# Analog_Light_Project_Improved_PCB.net
KiCad netlist of a schematic drawn in EAGLE
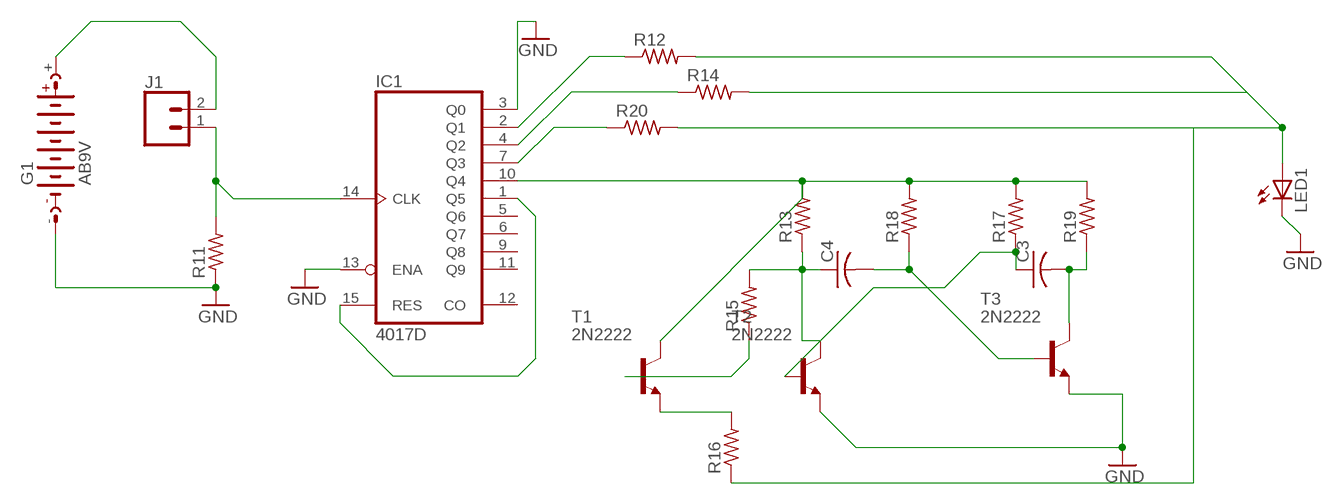
[diagram p0: schematic, sheet 1]

(export (version "E")
  (design (tool "Eeschema 10.0.6"))
  (components
    (comp (ref "C3")
      (value "C-USC0805")
      (footprint "eagle-import:C0805")
      (libsource (lib "eagle-import") (part "C-USC0805"))
    )
    (comp (ref "C4")
      (value "C-USC0805")
      (footprint "eagle-import:C0805")
      (libsource (lib "eagle-import") (part "C-USC0805"))
    )
    (comp (ref "G1")
      (value "AB9V")
      (footprint "eagle-import:AB9V")
      (libsource (lib "eagle-import") (part "AB9V"))
    )
    (comp (ref "IC1")
      (value "4017D")
      (footprint "eagle-import:SO16")
      (libsource (lib "eagle-import") (part "4017D"))
    )
    (comp (ref "J1")
      (value "CONN_02")
      (footprint "eagle-import:1X02")
      (libsource (lib "eagle-import") (part "CONN_02"))
    )
    (comp (ref "LED1")
      (value "LED5MM")
      (footprint "eagle-import:LED5MM")
      (libsource (lib "eagle-import") (part "LED5MM"))
    )
    (comp (ref "R11")
      (value "R-US_M0805")
      (footprint "eagle-import:M0805")
      (libsource (lib "eagle-import") (part "R-US_M0805"))
    )
    (comp (ref "R12")
      (value "R-US_M0805")
      (footprint "eagle-import:M0805")
      (libsource (lib "eagle-import") (part "R-US_M0805"))
    )
    (comp (ref "R13")
      (value "R-US_M0805")
      (footprint "eagle-import:M0805")
      (libsource (lib "eagle-import") (part "R-US_M0805"))
    )
    (comp (ref "R14")
      (value "R-US_M0805")
      (footprint "eagle-import:M0805")
      (libsource (lib "eagle-import") (part "R-US_M0805"))
    )
    (comp (ref "R15")
      (value "R-US_M0805")
      (footprint "eagle-import:M0805")
      (libsource (lib "eagle-import") (part "R-US_M0805"))
    )
    (comp (ref "R16")
      (value "R-US_M0805")
      (footprint "eagle-import:M0805")
      (libsource (lib "eagle-import") (part "R-US_M0805"))
    )
    (comp (ref "R17")
      (value "R-US_M0805")
      (footprint "eagle-import:M0805")
      (libsource (lib "eagle-import") (part "R-US_M0805"))
    )
    (comp (ref "R18")
      (value "R-US_M0805")
      (footprint "eagle-import:M0805")
      (libsource (lib "eagle-import") (part "R-US_M0805"))
    )
    (comp (ref "R19")
      (value "R-US_M0805")
      (footprint "eagle-import:M0805")
      (libsource (lib "eagle-import") (part "R-US_M0805"))
    )
    (comp (ref "R20")
      (value "R-US_M0805")
      (footprint "eagle-import:M0805")
      (libsource (lib "eagle-import") (part "R-US_M0805"))
    )
    (comp (ref "T1")
      (value "2N2222")
      (footprint "eagle-import:TO92-EBC-OVAL")
      (libsource (lib "eagle-import") (part "2N2222"))
    )
    (comp (ref "T2")
      (value "2N2222")
      (footprint "eagle-import:TO92-EBC-OVAL")
      (libsource (lib "eagle-import") (part "2N2222"))
    )
    (comp (ref "T3")
      (value "2N2222")
      (footprint "eagle-import:TO92-EBC-OVAL")
      (libsource (lib "eagle-import") (part "2N2222"))
    )
  )
  (nets
    (net (code "1") (name "GND") (class "Default")
      (node (ref "G1") (pin "-") (pinfunction "-_-") (pintype "passive"))
      (node (ref "IC1") (pin "13") (pinfunction "ENA_13") (pintype "input"))
      (node (ref "IC1") (pin "3") (pinfunction "Q0_3") (pintype "output"))
      (node (ref "LED1") (pin "K") (pinfunction "C_K") (pintype "passive"))
      (node (ref "R11") (pin "1") (pinfunction "1_1") (pintype "passive"))
      (node (ref "T2") (pin "E") (pinfunction "E_E") (pintype "passive"))
      (node (ref "T3") (pin "E") (pinfunction "E_E") (pintype "passive"))
    )
    (net (code "2") (name "Net-(C3-Pad1)") (class "Default")
      (node (ref "C3") (pin "1") (pinfunction "1_1") (pintype "passive"))
      (node (ref "R17") (pin "1") (pinfunction "1_1") (pintype "passive"))
      (node (ref "T2") (pin "B") (pinfunction "B_B") (pintype "passive"))
    )
    (net (code "3") (name "Net-(C3-Pad2)") (class "Default")
      (node (ref "C3") (pin "2") (pinfunction "2_2") (pintype "passive"))
      (node (ref "R19") (pin "1") (pinfunction "1_1") (pintype "passive"))
      (node (ref "T3") (pin "C") (pinfunction "C_C") (pintype "passive"))
    )
    (net (code "4") (name "Net-(C4-Pad1)") (class "Default")
      (node (ref "C4") (pin "1") (pinfunction "1_1") (pintype "passive"))
      (node (ref "R13") (pin "1") (pinfunction "1_1") (pintype "passive"))
      (node (ref "R15") (pin "2") (pinfunction "2_2") (pintype "passive"))
      (node (ref "T2") (pin "C") (pinfunction "C_C") (pintype "passive"))
    )
    (net (code "5") (name "Net-(C4-Pad2)") (class "Default")
      (node (ref "C4") (pin "2") (pinfunction "2_2") (pintype "passive"))
      (node (ref "R18") (pin "1") (pinfunction "1_1") (pintype "passive"))
      (node (ref "T3") (pin "B") (pinfunction "B_B") (pintype "passive"))
    )
    (net (code "6") (name "Net-(G1-Pad+)") (class "Default")
      (node (ref "G1") (pin "+") (pinfunction "+_+") (pintype "passive"))
      (node (ref "J1") (pin "2") (pinfunction "2_2") (pintype "passive"))
    )
    (net (code "7") (name "Net-(IC1A-CLK)") (class "Default")
      (node (ref "IC1") (pin "14") (pinfunction "CLK_14") (pintype "input"))
      (node (ref "J1") (pin "1") (pinfunction "1_1") (pintype "passive"))
      (node (ref "R11") (pin "2") (pinfunction "2_2") (pintype "passive"))
    )
    (net (code "8") (name "Net-(IC1A-Q1)") (class "Default")
      (node (ref "IC1") (pin "2") (pinfunction "Q1_2") (pintype "output"))
      (node (ref "R12") (pin "1") (pinfunction "1_1") (pintype "passive"))
    )
    (net (code "9") (name "Net-(IC1A-Q2)") (class "Default")
      (node (ref "IC1") (pin "4") (pinfunction "Q2_4") (pintype "output"))
      (node (ref "R14") (pin "1") (pinfunction "1_1") (pintype "passive"))
    )
    (net (code "10") (name "Net-(IC1A-Q3)") (class "Default")
      (node (ref "IC1") (pin "7") (pinfunction "Q3_7") (pintype "output"))
      (node (ref "R20") (pin "1") (pinfunction "1_1") (pintype "passive"))
    )
    (net (code "11") (name "Net-(IC1A-Q4)") (class "Default")
      (node (ref "IC1") (pin "10") (pinfunction "Q4_10") (pintype "output"))
      (node (ref "R13") (pin "2") (pinfunction "2_2") (pintype "passive"))
      (node (ref "R17") (pin "2") (pinfunction "2_2") (pintype "passive"))
      (node (ref "R18") (pin "2") (pinfunction "2_2") (pintype "passive"))
      (node (ref "R19") (pin "2") (pinfunction "2_2") (pintype "passive"))
      (node (ref "T1") (pin "C") (pinfunction "C_C") (pintype "passive"))
    )
    (net (code "12") (name "Net-(IC1A-Q5)") (class "Default")
      (node (ref "IC1") (pin "1") (pinfunction "Q5_1") (pintype "output"))
      (node (ref "IC1") (pin "15") (pinfunction "RES_15") (pintype "input"))
    )
    (net (code "13") (name "Net-(LED1-PadA)") (class "Default")
      (node (ref "LED1") (pin "A") (pinfunction "A_A") (pintype "passive"))
      (node (ref "R12") (pin "2") (pinfunction "2_2") (pintype "passive"))
      (node (ref "R14") (pin "2") (pinfunction "2_2") (pintype "passive"))
      (node (ref "R16") (pin "1") (pinfunction "1_1") (pintype "passive"))
      (node (ref "R20") (pin "2") (pinfunction "2_2") (pintype "passive"))
    )
    (net (code "14") (name "Net-(R15-Pad1)") (class "Default")
      (node (ref "R15") (pin "1") (pinfunction "1_1") (pintype "passive"))
      (node (ref "T1") (pin "B") (pinfunction "B_B") (pintype "passive"))
    )
    (net (code "15") (name "Net-(R16-Pad2)") (class "Default")
      (node (ref "R16") (pin "2") (pinfunction "2_2") (pintype "passive"))
      (node (ref "T1") (pin "E") (pinfunction "E_E") (pintype "passive"))
    )
    (net (code "16") (name "unconnected-(IC1A-CO-Pad12)") (class "Default")
      (node (ref "IC1") (pin "12") (pinfunction "CO_12") (pintype "output"))
    )
    (net (code "17") (name "unconnected-(IC1A-Q6-Pad5)") (class "Default")
      (node (ref "IC1") (pin "5") (pinfunction "Q6_5") (pintype "output"))
    )
    (net (code "18") (name "unconnected-(IC1A-Q7-Pad6)") (class "Default")
      (node (ref "IC1") (pin "6") (pinfunction "Q7_6") (pintype "output"))
    )
    (net (code "19") (name "unconnected-(IC1A-Q8-Pad9)") (class "Default")
      (node (ref "IC1") (pin "9") (pinfunction "Q8_9") (pintype "output"))
    )
    (net (code "20") (name "unconnected-(IC1A-Q9-Pad11)") (class "Default")
      (node (ref "IC1") (pin "11") (pinfunction "Q9_11") (pintype "output"))
    )
  )
)
